# VI_Sensors.net
KiCad netlist of a schematic drawn in Altium Designer
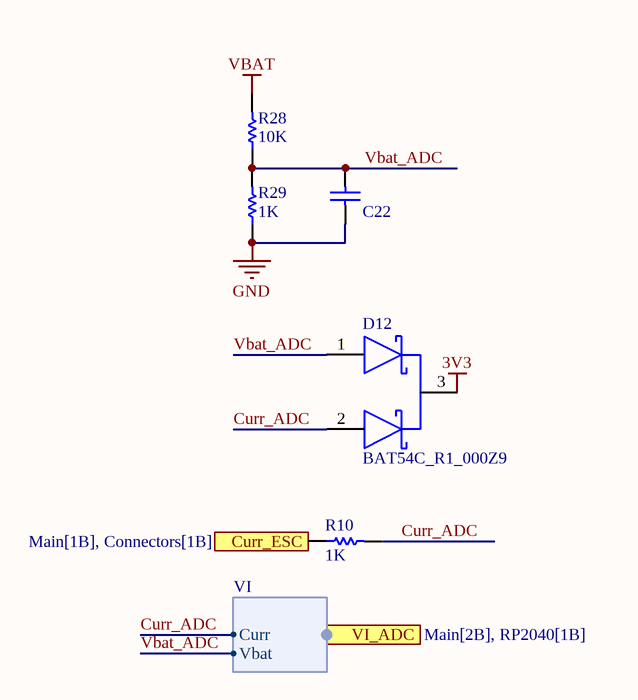
[diagram p0: VI Sensors.SchDoc]

(export (version "E")
  (design (tool "Eeschema 10.0.6"))
  (components
    (comp (ref "C22")
      (value "1µF")
      (footprint "WCAP-CSGP_0603_L1.6W0.8H0.8_Reflow")
      (description "WCAP-CSGP Multilayer Ceramic Chip Capacitor, General Purpose, size 0603, X5R, 1µF, 16VDC")
      (fields
        (field (name "MANUFACTURER PART NUMBER") "885012106017")
        (field (name "MANUFACTURER") "Wurth Elektronik")
      )
      (libsource (lib "Altium_WCAP-CSGP (rev22e)") (part "885012106017"))
    )
    (comp (ref "D12")
      (value "BAT54C_R1_000Z9")
      (footprint "FP-SOT23-MFG")
      (description "DIODE ARRAY SCHOTTKY 30V SOT23")
      (fields
        (field (name "MANUFACTURER") "Nexperia")
        (field (name "OCTOPART") "https://octopart.com/bat54c%2C215-nexperia-78738945")
      )
      (libsource (lib "Altium Content Vault") (part "933c91619b22c421400e34e7415f7b4"))
    )
    (comp (ref "R10")
      (value "1K")
      (footprint "RESC0603(1608)_N")
      (description "Chipwiderstand, SMD, Baureihe MC, 1%")
      (fields (field (name "MANUFACTURER") "Multicomp"))
      (libsource (lib "Standardbauteile") (part "Res 1K"))
    )
    (comp (ref "R28")
      (value "10K")
      (footprint "RESC0603(1608)_N")
      (description "Chipwiderstand, SMD, Baureihe MC, 1%")
      (fields (field (name "MANUFACTURER") "Multicomp"))
      (libsource (lib "Standardbauteile") (part "Res 100K"))
    )
    (comp (ref "R29")
      (value "1K")
      (footprint "RESC0603(1608)_N")
      (description "Chipwiderstand, SMD, Baureihe MC, 1%")
      (fields (field (name "MANUFACTURER") "Multicomp"))
      (libsource (lib "Standardbauteile") (part "Res 10K"))
    )
  )
  (nets
    (net (code "2") (name "/Curr_ADC") (class "Default")
      (node (ref "D12") (pin "2") (pinfunction "2_ANODE_2") (pintype "passive"))
      (node (ref "R10") (pin "2") (pinfunction "2_2") (pintype "passive"))
    )
    (net (code "3") (name "/Curr_ESC") (class "Default")
      (node (ref "R10") (pin "1") (pinfunction "1_1") (pintype "passive"))
    )
    (net (code "4") (name "/Vbat_ADC") (class "Default")
      (node (ref "C22") (pin "2") (pinfunction "2_2") (pintype "passive"))
      (node (ref "D12") (pin "1") (pinfunction "1_ANODE_1") (pintype "passive"))
      (node (ref "R28") (pin "1") (pinfunction "1_1") (pintype "passive"))
      (node (ref "R29") (pin "2") (pinfunction "2_2") (pintype "passive"))
    )
    (net (code "6") (name "3V3") (class "Default")
      (node (ref "D12") (pin "3") (pinfunction "COMMON_CATHODE_3") (pintype "passive"))
    )
    (net (code "7") (name "GND") (class "Default")
      (node (ref "C22") (pin "1") (pinfunction "1_1") (pintype "passive"))
      (node (ref "R29") (pin "1") (pinfunction "1_1") (pintype "passive"))
    )
    (net (code "8") (name "VBAT") (class "Default")
      (node (ref "R28") (pin "2") (pinfunction "2_2") (pintype "passive"))
    )
  )
)
